# KorszeRT.net
KiCad netlist of a schematic drawn in Altium Designer
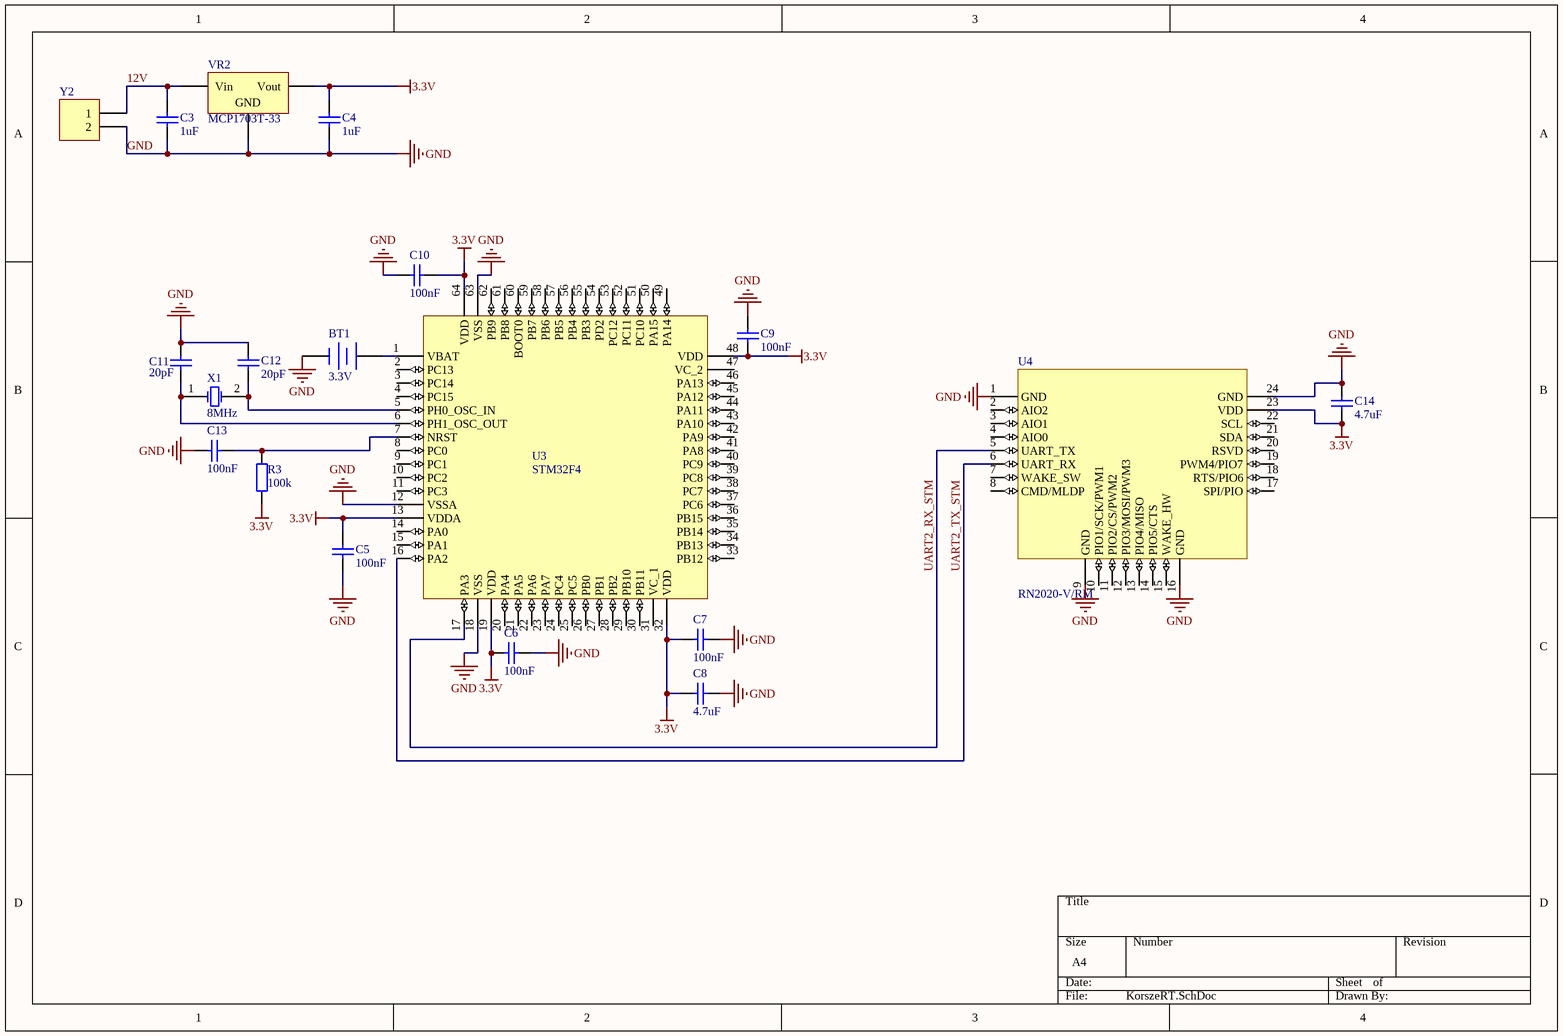
[diagram p0: KorszeRT.SchDoc]

(export (version "E")
  (design (tool "Eeschema 10.0.6"))
  (components
    (comp (ref "BT1")
      (value "3.3V")
      (footprint "BAT-2")
      (description "Multicell Battery")
      (fields (field (name "PUBLISHER") "Altium Limited"))
      (libsource (lib "Miscellaneous Devices") (part "Battery"))
    )
    (comp (ref "C3")
      (value "1uF")
      (footprint "RAD-0.3")
      (description "Capacitor")
      (fields (field (name "PUBLISHER") "Altium Limited"))
      (libsource (lib "Miscellaneous Devices") (part "Cap"))
    )
    (comp (ref "C4")
      (value "1uF")
      (footprint "RAD-0.3")
      (description "Capacitor")
      (fields (field (name "PUBLISHER") "Altium Limited"))
      (libsource (lib "Miscellaneous Devices") (part "Cap"))
    )
    (comp (ref "C5")
      (value "100nF")
      (footprint "RAD-0.3")
      (description "Capacitor")
      (fields (field (name "PUBLISHER") "Altium Limited"))
      (libsource (lib "Miscellaneous Devices") (part "Cap"))
    )
    (comp (ref "C6")
      (value "100nF")
      (footprint "RAD-0.3")
      (description "Capacitor")
      (fields (field (name "PUBLISHER") "Altium Limited"))
      (libsource (lib "Miscellaneous Devices") (part "Cap"))
    )
    (comp (ref "C7")
      (value "100nF")
      (footprint "RAD-0.3")
      (description "Capacitor")
      (fields (field (name "PUBLISHER") "Altium Limited"))
      (libsource (lib "Miscellaneous Devices") (part "Cap"))
    )
    (comp (ref "C8")
      (value "4.7uF")
      (footprint "RAD-0.3")
      (description "Capacitor")
      (fields (field (name "PUBLISHER") "Altium Limited"))
      (libsource (lib "Miscellaneous Devices") (part "Cap"))
    )
    (comp (ref "C9")
      (value "100nF")
      (footprint "RAD-0.3")
      (description "Capacitor")
      (fields (field (name "PUBLISHER") "Altium Limited"))
      (libsource (lib "Miscellaneous Devices") (part "Cap"))
    )
    (comp (ref "C10")
      (value "100nF")
      (footprint "RAD-0.3")
      (description "Capacitor")
      (fields (field (name "PUBLISHER") "Altium Limited"))
      (libsource (lib "Miscellaneous Devices") (part "Cap"))
    )
    (comp (ref "C11")
      (value "20pF")
      (footprint "RAD-0.3")
      (description "Capacitor")
      (fields (field (name "PUBLISHER") "Altium Limited"))
      (libsource (lib "Miscellaneous Devices") (part "Cap"))
    )
    (comp (ref "C12")
      (value "20pF")
      (footprint "RAD-0.3")
      (description "Capacitor")
      (fields (field (name "PUBLISHER") "Altium Limited"))
      (libsource (lib "Miscellaneous Devices") (part "Cap"))
    )
    (comp (ref "C13")
      (value "100nF")
      (footprint "RAD-0.3")
      (description "Capacitor")
      (fields (field (name "PUBLISHER") "Altium Limited"))
      (libsource (lib "Miscellaneous Devices") (part "Cap"))
    )
    (comp (ref "C14")
      (value "4.7uF")
      (footprint "RAD-0.3")
      (description "Capacitor")
      (fields (field (name "PUBLISHER") "Altium Limited"))
      (libsource (lib "Miscellaneous Devices") (part "Cap"))
    )
    (comp (ref "R3")
      (value "100k")
      (footprint "AXIAL-0.4")
      (description "Resistor")
      (fields (field (name "PUBLISHER") "Altium Limited"))
      (libsource (lib "Miscellaneous Devices") (part "Res2"))
    )
    (comp (ref "U3")
      (value "STM32F4")
      (footprint "TQFP64_M")
      (description "STM32F405RGT6")
      (libsource (lib "STM32F4") (part "STM32F405RGT6"))
    )
    (comp (ref "U4")
      (value "RN2020-V/RM")
      (footprint "RN4020 MODULE-24")
      (description "Microchip RN4020 Bluetooth")
      (libsource (lib "MicrochipTechnology") (part "RN2020-V/RM123"))
    )
    (comp (ref "VR2")
      (value "MCP1703T-33")
      (footprint "SOT23_M")
      (description "Voltage Regulator")
      (fields (field (name "PUBLISHER") "Altium Limited"))
      (libsource (lib "Miscellaneous Devices") (part "Volt Reg"))
    )
    (comp (ref "X1")
      (value "8MHz")
      (footprint "R38")
      (description "Crystal Oscillator")
      (fields (field (name "PUBLISHER") "Altium Limited"))
      (libsource (lib "Miscellaneous Devices") (part "XTAL"))
    )
    (comp (ref "Y2")
      (value "Header 2H")
      (footprint "HDR1X2H")
      (description "Header, 2-Pin, Right Angle")
      (fields (field (name "PUBLISHER") "Altium Limited"))
      (libsource (lib "Miscellaneous Connectors") (part "Header 2H"))
    )
  )
  (nets
    (net (code "1") (name "/12V") (class "Default")
      (node (ref "C3") (pin "2") (pinfunction "2_2") (pintype "passive"))
      (node (ref "VR2") (pin "1") (pinfunction "Vin_1") (pintype "passive"))
      (node (ref "Y2") (pin "1") (pinfunction "1_1") (pintype "passive"))
    )
    (net (code "2") (name "/UART2_RX_STM") (class "Default")
      (node (ref "U3") (pin "17") (pinfunction "PA3_17") (pintype "bidirectional"))
      (node (ref "U4") (pin "5") (pinfunction "UART_TX_5") (pintype "bidirectional"))
    )
    (net (code "3") (name "/UART2_TX_STM") (class "Default")
      (node (ref "U3") (pin "16") (pinfunction "PA2_16") (pintype "bidirectional"))
      (node (ref "U4") (pin "6") (pinfunction "UART_RX_6") (pintype "bidirectional"))
    )
    (net (code "4") (name "3.3V") (class "Default")
      (node (ref "C10") (pin "2") (pinfunction "2_2") (pintype "passive"))
      (node (ref "C14") (pin "1") (pinfunction "1_1") (pintype "passive"))
      (node (ref "C4") (pin "2") (pinfunction "2_2") (pintype "passive"))
      (node (ref "C5") (pin "2") (pinfunction "2_2") (pintype "passive"))
      (node (ref "C6") (pin "2") (pinfunction "2_2") (pintype "passive"))
      (node (ref "C7") (pin "2") (pinfunction "2_2") (pintype "passive"))
      (node (ref "C8") (pin "1") (pinfunction "1_1") (pintype "passive"))
      (node (ref "C9") (pin "1") (pinfunction "1_1") (pintype "passive"))
      (node (ref "R3") (pin "2") (pinfunction "2_2") (pintype "passive"))
      (node (ref "U3") (pin "13") (pinfunction "VDDA_13") (pintype "passive"))
      (node (ref "U3") (pin "19") (pinfunction "VDD_19") (pintype "power_in"))
      (node (ref "U3") (pin "32") (pinfunction "VDD_32") (pintype "power_in"))
      (node (ref "U3") (pin "48") (pinfunction "VDD_48") (pintype "power_in"))
      (node (ref "U3") (pin "64") (pinfunction "VDD_64") (pintype "power_in"))
      (node (ref "U4") (pin "23") (pinfunction "VDD_23") (pintype "power_in"))
      (node (ref "VR2") (pin "3") (pinfunction "Vout_3") (pintype "passive"))
    )
    (net (code "5") (name "GND") (class "Default")
      (node (ref "BT1") (pin "2") (pinfunction "-_2") (pintype "passive"))
      (node (ref "C10") (pin "1") (pinfunction "1_1") (pintype "passive"))
      (node (ref "C11") (pin "2") (pinfunction "2_2") (pintype "passive"))
      (node (ref "C12") (pin "2") (pinfunction "2_2") (pintype "passive"))
      (node (ref "C13") (pin "2") (pinfunction "2_2") (pintype "passive"))
      (node (ref "C14") (pin "2") (pinfunction "2_2") (pintype "passive"))
      (node (ref "C3") (pin "1") (pinfunction "1_1") (pintype "passive"))
      (node (ref "C4") (pin "1") (pinfunction "1_1") (pintype "passive"))
      (node (ref "C5") (pin "1") (pinfunction "1_1") (pintype "passive"))
      (node (ref "C6") (pin "1") (pinfunction "1_1") (pintype "passive"))
      (node (ref "C7") (pin "1") (pinfunction "1_1") (pintype "passive"))
      (node (ref "C8") (pin "2") (pinfunction "2_2") (pintype "passive"))
      (node (ref "C9") (pin "2") (pinfunction "2_2") (pintype "passive"))
      (node (ref "U3") (pin "12") (pinfunction "VSSA_12") (pintype "passive"))
      (node (ref "U3") (pin "18") (pinfunction "VSS_18") (pintype "power_in"))
      (node (ref "U3") (pin "63") (pinfunction "VSS_63") (pintype "power_in"))
      (node (ref "U4") (pin "1") (pinfunction "GND_1") (pintype "power_in"))
      (node (ref "U4") (pin "16") (pinfunction "GND_16") (pintype "power_in"))
      (node (ref "U4") (pin "24") (pinfunction "GND_24") (pintype "power_in"))
      (node (ref "U4") (pin "9") (pinfunction "GND_9") (pintype "power_in"))
      (node (ref "VR2") (pin "2") (pinfunction "GND_2") (pintype "passive"))
      (node (ref "Y2") (pin "2") (pinfunction "2_2") (pintype "passive"))
    )
    (net (code "6") (name "Net-(BT1-+)") (class "Default")
      (node (ref "BT1") (pin "1") (pinfunction "+_1") (pintype "passive"))
      (node (ref "U3") (pin "1") (pinfunction "VBAT_1") (pintype "power_in"))
    )
    (net (code "7") (name "Net-(U3-NRST)") (class "Default")
      (node (ref "C13") (pin "1") (pinfunction "1_1") (pintype "passive"))
      (node (ref "R3") (pin "1") (pinfunction "1_1") (pintype "passive"))
      (node (ref "U3") (pin "7") (pinfunction "NRST_7") (pintype "bidirectional"))
    )
    (net (code "8") (name "Net-(U3-PH0_OSC_IN)") (class "Default")
      (node (ref "C12") (pin "1") (pinfunction "1_1") (pintype "passive"))
      (node (ref "U3") (pin "5") (pinfunction "PH0_OSC_IN_5") (pintype "bidirectional"))
      (node (ref "X1") (pin "2") (pinfunction "OSC2_2") (pintype "passive"))
    )
    (net (code "9") (name "Net-(U3-PH1_OSC_OUT)") (class "Default")
      (node (ref "C11") (pin "1") (pinfunction "1_1") (pintype "passive"))
      (node (ref "U3") (pin "6") (pinfunction "PH1_OSC_OUT_6") (pintype "bidirectional"))
      (node (ref "X1") (pin "1") (pinfunction "OSC1_1") (pintype "passive"))
    )
    (net (code "10") (name "unconnected-(U3-BOOT0-Pad60)") (class "Default")
      (node (ref "U3") (pin "60") (pinfunction "BOOT0_60") (pintype "bidirectional"))
    )
    (net (code "11") (name "unconnected-(U3-PA0-Pad14)") (class "Default")
      (node (ref "U3") (pin "14") (pinfunction "PA0_14") (pintype "bidirectional"))
    )
    (net (code "12") (name "unconnected-(U3-PA1-Pad15)") (class "Default")
      (node (ref "U3") (pin "15") (pinfunction "PA1_15") (pintype "bidirectional"))
    )
    (net (code "13") (name "unconnected-(U3-PA4-Pad20)") (class "Default")
      (node (ref "U3") (pin "20") (pinfunction "PA4_20") (pintype "bidirectional"))
    )
    (net (code "14") (name "unconnected-(U3-PA5-Pad21)") (class "Default")
      (node (ref "U3") (pin "21") (pinfunction "PA5_21") (pintype "bidirectional"))
    )
    (net (code "15") (name "unconnected-(U3-PA6-Pad22)") (class "Default")
      (node (ref "U3") (pin "22") (pinfunction "PA6_22") (pintype "bidirectional"))
    )
    (net (code "16") (name "unconnected-(U3-PA7-Pad23)") (class "Default")
      (node (ref "U3") (pin "23") (pinfunction "PA7_23") (pintype "bidirectional"))
    )
    (net (code "17") (name "unconnected-(U3-PA8-Pad41)") (class "Default")
      (node (ref "U3") (pin "41") (pinfunction "PA8_41") (pintype "bidirectional"))
    )
    (net (code "18") (name "unconnected-(U3-PA9-Pad42)") (class "Default")
      (node (ref "U3") (pin "42") (pinfunction "PA9_42") (pintype "bidirectional"))
    )
    (net (code "19") (name "unconnected-(U3-PA10-Pad43)") (class "Default")
      (node (ref "U3") (pin "43") (pinfunction "PA10_43") (pintype "bidirectional"))
    )
    (net (code "20") (name "unconnected-(U3-PA11-Pad44)") (class "Default")
      (node (ref "U3") (pin "44") (pinfunction "PA11_44") (pintype "bidirectional"))
    )
    (net (code "21") (name "unconnected-(U3-PA12-Pad45)") (class "Default")
      (node (ref "U3") (pin "45") (pinfunction "PA12_45") (pintype "bidirectional"))
    )
    (net (code "22") (name "unconnected-(U3-PA13-Pad46)") (class "Default")
      (node (ref "U3") (pin "46") (pinfunction "PA13_46") (pintype "bidirectional"))
    )
    (net (code "23") (name "unconnected-(U3-PA14-Pad49)") (class "Default")
      (node (ref "U3") (pin "49") (pinfunction "PA14_49") (pintype "bidirectional"))
    )
    (net (code "24") (name "unconnected-(U3-PA15-Pad50)") (class "Default")
      (node (ref "U3") (pin "50") (pinfunction "PA15_50") (pintype "bidirectional"))
    )
    (net (code "25") (name "unconnected-(U3-PB0-Pad26)") (class "Default")
      (node (ref "U3") (pin "26") (pinfunction "PB0_26") (pintype "bidirectional"))
    )
    (net (code "26") (name "unconnected-(U3-PB1-Pad27)") (class "Default")
      (node (ref "U3") (pin "27") (pinfunction "PB1_27") (pintype "bidirectional"))
    )
    (net (code "27") (name "unconnected-(U3-PB2-Pad28)") (class "Default")
      (node (ref "U3") (pin "28") (pinfunction "PB2_28") (pintype "bidirectional"))
    )
    (net (code "28") (name "unconnected-(U3-PB3-Pad55)") (class "Default")
      (node (ref "U3") (pin "55") (pinfunction "PB3_55") (pintype "bidirectional"))
    )
    (net (code "29") (name "unconnected-(U3-PB4-Pad56)") (class "Default")
      (node (ref "U3") (pin "56") (pinfunction "PB4_56") (pintype "bidirectional"))
    )
    (net (code "30") (name "unconnected-(U3-PB5-Pad57)") (class "Default")
      (node (ref "U3") (pin "57") (pinfunction "PB5_57") (pintype "bidirectional"))
    )
    (net (code "31") (name "unconnected-(U3-PB6-Pad58)") (class "Default")
      (node (ref "U3") (pin "58") (pinfunction "PB6_58") (pintype "bidirectional"))
    )
    (net (code "32") (name "unconnected-(U3-PB7-Pad59)") (class "Default")
      (node (ref "U3") (pin "59") (pinfunction "PB7_59") (pintype "bidirectional"))
    )
    (net (code "33") (name "unconnected-(U3-PB8-Pad61)") (class "Default")
      (node (ref "U3") (pin "61") (pinfunction "PB8_61") (pintype "bidirectional"))
    )
    (net (code "34") (name "unconnected-(U3-PB9-Pad62)") (class "Default")
      (node (ref "U3") (pin "62") (pinfunction "PB9_62") (pintype "bidirectional"))
    )
    (net (code "35") (name "unconnected-(U3-PB10-Pad29)") (class "Default")
      (node (ref "U3") (pin "29") (pinfunction "PB10_29") (pintype "bidirectional"))
    )
    (net (code "36") (name "unconnected-(U3-PB11-Pad30)") (class "Default")
      (node (ref "U3") (pin "30") (pinfunction "PB11_30") (pintype "bidirectional"))
    )
    (net (code "37") (name "unconnected-(U3-PB12-Pad33)") (class "Default")
      (node (ref "U3") (pin "33") (pinfunction "PB12_33") (pintype "bidirectional"))
    )
    (net (code "38") (name "unconnected-(U3-PB13-Pad34)") (class "Default")
      (node (ref "U3") (pin "34") (pinfunction "PB13_34") (pintype "bidirectional"))
    )
    (net (code "39") (name "unconnected-(U3-PB14-Pad35)") (class "Default")
      (node (ref "U3") (pin "35") (pinfunction "PB14_35") (pintype "bidirectional"))
    )
    (net (code "40") (name "unconnected-(U3-PB15-Pad36)") (class "Default")
      (node (ref "U3") (pin "36") (pinfunction "PB15_36") (pintype "bidirectional"))
    )
    (net (code "41") (name "unconnected-(U3-PC0-Pad8)") (class "Default")
      (node (ref "U3") (pin "8") (pinfunction "PC0_8") (pintype "bidirectional"))
    )
    (net (code "42") (name "unconnected-(U3-PC1-Pad9)") (class "Default")
      (node (ref "U3") (pin "9") (pinfunction "PC1_9") (pintype "bidirectional"))
    )
    (net (code "43") (name "unconnected-(U3-PC2-Pad10)") (class "Default")
      (node (ref "U3") (pin "10") (pinfunction "PC2_10") (pintype "bidirectional"))
    )
    (net (code "44") (name "unconnected-(U3-PC3-Pad11)") (class "Default")
      (node (ref "U3") (pin "11") (pinfunction "PC3_11") (pintype "bidirectional"))
    )
    (net (code "45") (name "unconnected-(U3-PC4-Pad24)") (class "Default")
      (node (ref "U3") (pin "24") (pinfunction "PC4_24") (pintype "bidirectional"))
    )
    (net (code "46") (name "unconnected-(U3-PC5-Pad25)") (class "Default")
      (node (ref "U3") (pin "25") (pinfunction "PC5_25") (pintype "bidirectional"))
    )
    (net (code "47") (name "unconnected-(U3-PC6-Pad37)") (class "Default")
      (node (ref "U3") (pin "37") (pinfunction "PC6_37") (pintype "bidirectional"))
    )
    (net (code "48") (name "unconnected-(U3-PC7-Pad38)") (class "Default")
      (node (ref "U3") (pin "38") (pinfunction "PC7_38") (pintype "bidirectional"))
    )
    (net (code "49") (name "unconnected-(U3-PC8-Pad39)") (class "Default")
      (node (ref "U3") (pin "39") (pinfunction "PC8_39") (pintype "bidirectional"))
    )
    (net (code "50") (name "unconnected-(U3-PC9-Pad40)") (class "Default")
      (node (ref "U3") (pin "40") (pinfunction "PC9_40") (pintype "bidirectional"))
    )
    (net (code "51") (name "unconnected-(U3-PC10-Pad51)") (class "Default")
      (node (ref "U3") (pin "51") (pinfunction "PC10_51") (pintype "bidirectional"))
    )
    (net (code "52") (name "unconnected-(U3-PC11-Pad52)") (class "Default")
      (node (ref "U3") (pin "52") (pinfunction "PC11_52") (pintype "bidirectional"))
    )
    (net (code "53") (name "unconnected-(U3-PC12-Pad53)") (class "Default")
      (node (ref "U3") (pin "53") (pinfunction "PC12_53") (pintype "bidirectional"))
    )
    (net (code "54") (name "unconnected-(U3-PC13-Pad2)") (class "Default")
      (node (ref "U3") (pin "2") (pinfunction "PC13_2") (pintype "bidirectional"))
    )
    (net (code "55") (name "unconnected-(U3-PC14-Pad3)") (class "Default")
      (node (ref "U3") (pin "3") (pinfunction "PC14_3") (pintype "bidirectional"))
    )
    (net (code "56") (name "unconnected-(U3-PC15-Pad4)") (class "Default")
      (node (ref "U3") (pin "4") (pinfunction "PC15_4") (pintype "bidirectional"))
    )
    (net (code "57") (name "unconnected-(U3-PD2-Pad54)") (class "Default")
      (node (ref "U3") (pin "54") (pinfunction "PD2_54") (pintype "bidirectional"))
    )
    (net (code "58") (name "unconnected-(U3-VC_1-Pad31)") (class "Default")
      (node (ref "U3") (pin "31") (pinfunction "VC_1_31") (pintype "power_in"))
    )
    (net (code "59") (name "unconnected-(U3-VC_2-Pad47)") (class "Default")
      (node (ref "U3") (pin "47") (pinfunction "VC_2_47") (pintype "power_in"))
    )
    (net (code "60") (name "unconnected-(U4-AIO0-Pad4)") (class "Default")
      (node (ref "U4") (pin "4") (pinfunction "AIO0_4") (pintype "bidirectional"))
    )
    (net (code "61") (name "unconnected-(U4-AIO1-Pad3)") (class "Default")
      (node (ref "U4") (pin "3") (pinfunction "AIO1_3") (pintype "bidirectional"))
    )
    (net (code "62") (name "unconnected-(U4-AIO2-Pad2)") (class "Default")
      (node (ref "U4") (pin "2") (pinfunction "AIO2_2") (pintype "bidirectional"))
    )
    (net (code "63") (name "unconnected-(U4-CMD{slash}MLDP-Pad8)") (class "Default")
      (node (ref "U4") (pin "8") (pinfunction "CMD/MLDP_8") (pintype "bidirectional"))
    )
    (net (code "64") (name "unconnected-(U4-PIO1{slash}SCK{slash}PWM1-Pad10)") (class "Default")
      (node (ref "U4") (pin "10") (pinfunction "PIO1/SCK/PWM1_10") (pintype "bidirectional"))
    )
    (net (code "65") (name "unconnected-(U4-PIO2{slash}CS{slash}PWM2-Pad11)") (class "Default")
      (node (ref "U4") (pin "11") (pinfunction "PIO2/CS/PWM2_11") (pintype "bidirectional"))
    )
    (net (code "66") (name "unconnected-(U4-PIO3{slash}MOSI{slash}PWM3-Pad12)") (class "Default")
      (node (ref "U4") (pin "12") (pinfunction "PIO3/MOSI/PWM3_12") (pintype "bidirectional"))
    )
    (net (code "67") (name "unconnected-(U4-PIO4{slash}MISO-Pad13)") (class "Default")
      (node (ref "U4") (pin "13") (pinfunction "PIO4/MISO_13") (pintype "bidirectional"))
    )
    (net (code "68") (name "unconnected-(U4-PIO5{slash}CTS-Pad14)") (class "Default")
      (node (ref "U4") (pin "14") (pinfunction "PIO5/CTS_14") (pintype "bidirectional"))
    )
    (net (code "69") (name "unconnected-(U4-PWM4{slash}PIO7-Pad19)") (class "Default")
      (node (ref "U4") (pin "19") (pinfunction "PWM4/PIO7_19") (pintype "bidirectional"))
    )
    (net (code "70") (name "unconnected-(U4-RSVD-Pad20)") (class "Default")
      (node (ref "U4") (pin "20") (pinfunction "RSVD_20") (pintype "bidirectional"))
    )
    (net (code "71") (name "unconnected-(U4-RTS{slash}PIO6-Pad18)") (class "Default")
      (node (ref "U4") (pin "18") (pinfunction "RTS/PIO6_18") (pintype "bidirectional"))
    )
    (net (code "72") (name "unconnected-(U4-SCL-Pad22)") (class "Default")
      (node (ref "U4") (pin "22") (pinfunction "SCL_22") (pintype "bidirectional"))
    )
    (net (code "73") (name "unconnected-(U4-SDA-Pad21)") (class "Default")
      (node (ref "U4") (pin "21") (pinfunction "SDA_21") (pintype "bidirectional"))
    )
    (net (code "74") (name "unconnected-(U4-SPI{slash}PIO-Pad17)") (class "Default")
      (node (ref "U4") (pin "17") (pinfunction "SPI/PIO_17") (pintype "bidirectional"))
    )
    (net (code "75") (name "unconnected-(U4-WAKE_HW-Pad15)") (class "Default")
      (node (ref "U4") (pin "15") (pinfunction "WAKE_HW_15") (pintype "bidirectional"))
    )
    (net (code "76") (name "unconnected-(U4-WAKE_SW-Pad7)") (class "Default")
      (node (ref "U4") (pin "7") (pinfunction "WAKE_SW_7") (pintype "bidirectional"))
    )
  )
)
